# Sheet1.net
KiCad netlist of a schematic drawn in Altium Designer
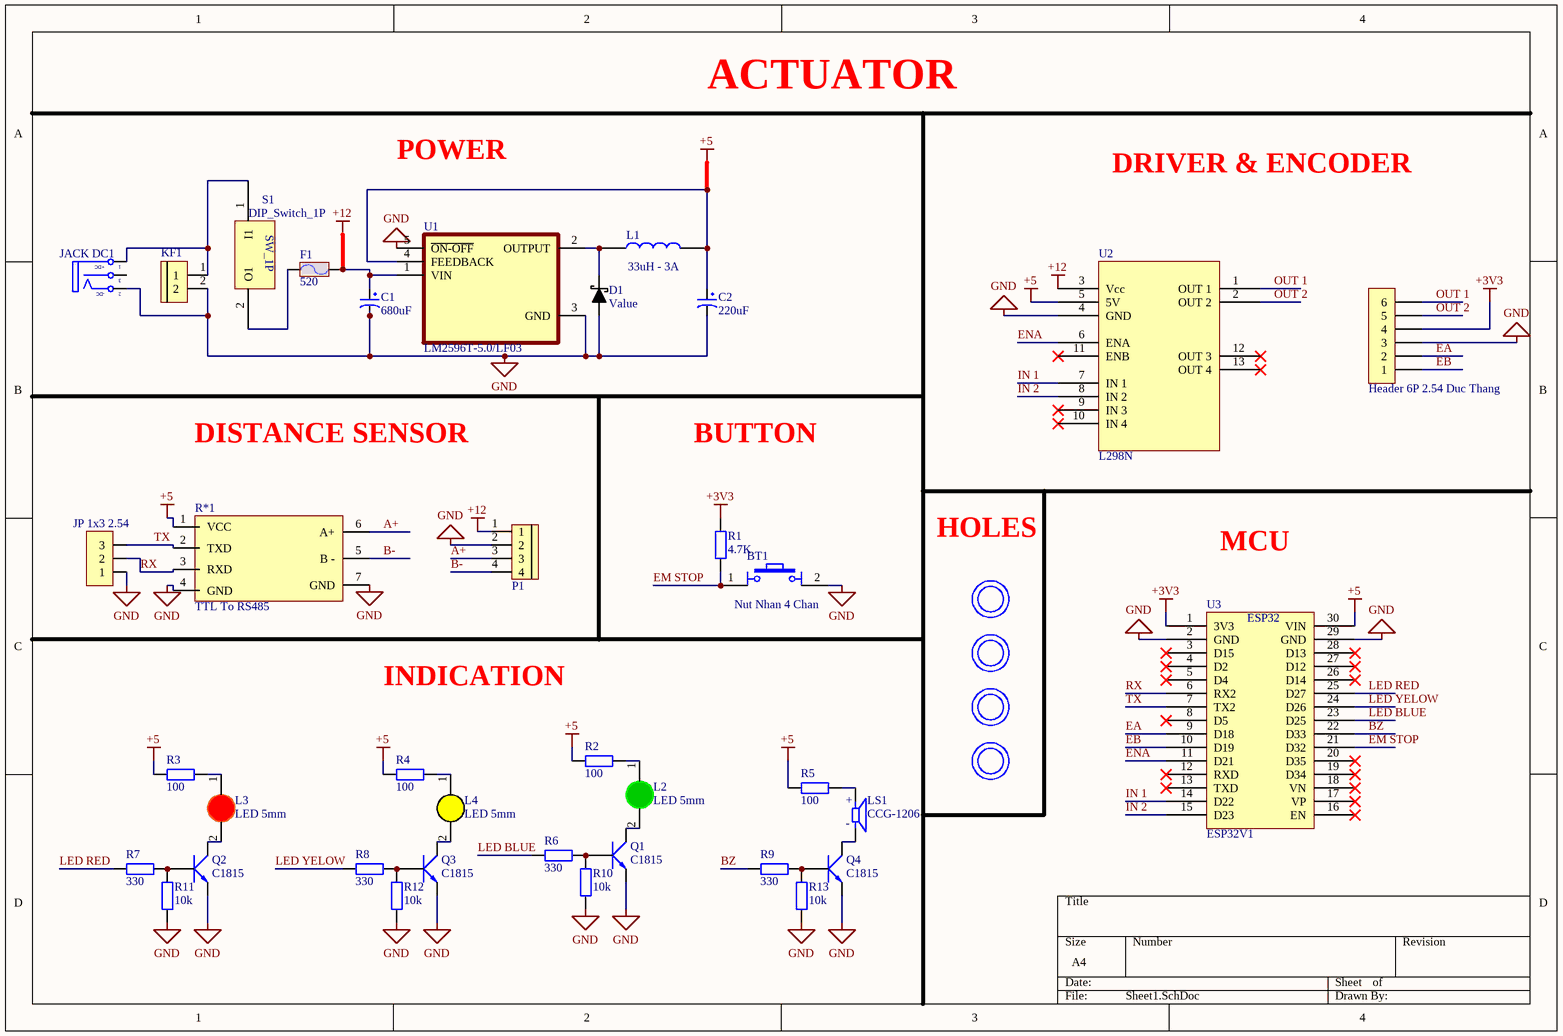
[diagram p0: Sheet1.SchDoc]

(export (version "E")
  (design (tool "Eeschema 10.0.6"))
  (components
    (comp (ref "1")
      (value "Hole")
      (footprint "Hole")
      (description "cắm")
      (libsource (lib "Thinh") (part "Hole"))
    )
    (comp (ref "2")
      (value "Hole")
      (footprint "Hole")
      (description "cắm")
      (libsource (lib "Thinh") (part "Hole"))
    )
    (comp (ref "3")
      (value "Hole")
      (footprint "Hole")
      (description "cắm")
      (libsource (lib "Thinh") (part "Hole"))
    )
    (comp (ref "4")
      (value "Hole")
      (footprint "Hole")
      (description "cắm")
      (libsource (lib "Thinh") (part "Hole"))
    )
    (comp (ref "BT1")
      (value "Nut Nhan 4 Chan")
      (footprint "Nut Nhan 4 Chan Cam 6x6")
      (description "Nut Nhan 4 Chan 6x6mm")
      (libsource (lib "Component") (part "Nut Nhan 4 Chan Cam 6x6"))
    )
    (comp (ref "C1")
      (value "680uF")
      (footprint "tu hoa 13mm")
      (description "Cắm")
      (libsource (lib "Tu dien") (part "Tu Hoa 680uF 25V 13x17"))
    )
    (comp (ref "C2")
      (value "220uF")
      (footprint "tu hoa 6.5mm")
      (description "Cắm")
      (libsource (lib "Tu dien") (part "Tu Hoa 220uF 16V 7x11"))
    )
    (comp (ref "D1")
      (value "Value")
      (footprint "DIODE_SMALL")
      (libsource (lib "Library_Ngocctu") (part "Diode schottky"))
    )
    (comp (ref "F1")
      (value "520")
      (footprint "De Cau Chi 520 630")
      (description "5x20mm")
      (libsource (lib "Component") (part "De Cau Chi 520 630"))
    )
    (comp (ref "H1")
      (value "Header 6P 2.54 Duc Thang")
      (footprint "XH2.54M-6")
      (description "Cắm")
      (libsource (lib "Header") (part "Header 6P 2.54 Duc Thang"))
    )
    (comp (ref "JACK DC1")
      (value "JACK DC 5.5")
      (footprint "JACK DC 5.5")
      (libsource (lib "Component") (part "JACK DC 5.5"))
    )
    (comp (ref "JP1")
      (value "JP 1x3 2.54")
      (footprint "JP 1x3 DT")
      (description "Cắm")
      (libsource (lib "Jump") (part "JP 1x3 2.54 Duc Thang"))
    )
    (comp (ref "KF1")
      (value "CON 2 KF301")
      (footprint "Con 2 KF301 5.08")
      (description "Cắm")
      (libsource (lib "Connector") (part "CON 2 KF301"))
    )
    (comp (ref "L1")
      (value "33uH - 3A")
      (footprint "CUON CAM 100uH3A")
      (description "Cắm")
      (libsource (lib "Cuon Cam") (part "CUON CAM 470uH DIP"))
    )
    (comp (ref "L2")
      (value "LED 5mm")
      (footprint "LED-5MM-Green")
      (description "Cắm")
      (libsource (lib "Led") (part "LED 5mm Xanh La"))
    )
    (comp (ref "L3")
      (value "LED 5mm")
      (footprint "LED-5MM-RED")
      (description "Cắm")
      (libsource (lib "Led") (part "LED 5mm Do"))
    )
    (comp (ref "L4")
      (value "LED 5mm")
      (footprint "LED-5MM-Yellow")
      (description "Cắm")
      (libsource (lib "Led") (part "LED 5mm Vang"))
    )
    (comp (ref "LS1")
      (value "CCG-1206")
      (footprint "CUI_CCG-1206")
      (description "12 mm, 5 V, 85 dB, Through Hole, Sealed, Magnetic Audio Transducer Buzzer")
      (fields (field (name "MF") "Same Sky"))
      (libsource (lib "Thinh") (part "CCG-1206"))
    )
    (comp (ref "P1")
      (value "CON 4 EDG5.08")
      (footprint "CON 4 4EDG5.08 - THANG")
      (description "Cắm")
      (libsource (lib "Connector") (part "CON 4 EDG5.08"))
    )
    (comp (ref "Q1")
      (value "C1815")
      (footprint "TO92")
      (description "NPN transistor")
      (libsource (lib "TranFet") (part "C1815"))
    )
    (comp (ref "Q2")
      (value "C1815")
      (footprint "TO92")
      (description "NPN transistor")
      (libsource (lib "TranFet") (part "C1815"))
    )
    (comp (ref "Q3")
      (value "C1815")
      (footprint "TO92")
      (description "NPN transistor")
      (libsource (lib "TranFet") (part "C1815"))
    )
    (comp (ref "Q4")
      (value "C1815")
      (footprint "TO92")
      (description "NPN transistor")
      (libsource (lib "TranFet") (part "C1815"))
    )
    (comp (ref "R*1")
      (value "TTL To RS485")
      (footprint "TTL TO RS485_Module")
      (libsource (lib "NGUYENDAINGHIA") (part "TTL To RS485"))
    )
    (comp (ref "R1")
      (value "4.7K")
      (footprint "tro vach 1/4w")
      (description "Cắm")
      (libsource (lib "Dien Tro") (part "Tro Vach 1/4W 5% 100R"))
    )
    (comp (ref "R2")
      (value "100")
      (footprint "tro vach 1/4w")
      (description "Cắm")
      (libsource (lib "Dien Tro") (part "Tro Vach 1/4W 5% 100R"))
    )
    (comp (ref "R3")
      (value "100")
      (footprint "tro vach 1/4w")
      (description "Cắm")
      (libsource (lib "Dien Tro") (part "Tro Vach 1/4W 5% 100R"))
    )
    (comp (ref "R4")
      (value "100")
      (footprint "tro vach 1/4w")
      (description "Cắm")
      (libsource (lib "Dien Tro") (part "Tro Vach 1/4W 5% 100R"))
    )
    (comp (ref "R5")
      (value "100")
      (footprint "tro vach 1/4w")
      (description "Cắm")
      (libsource (lib "Dien Tro") (part "Tro Vach 1/4W 5% 100R"))
    )
    (comp (ref "R6")
      (value "330")
      (footprint "tro vach 1/4w")
      (description "Cắm")
      (libsource (lib "Dien Tro") (part "Tro Vach 1/4W 5% 100R"))
    )
    (comp (ref "R7")
      (value "330")
      (footprint "tro vach 1/4w")
      (description "Cắm")
      (libsource (lib "Dien Tro") (part "Tro Vach 1/4W 5% 100R"))
    )
    (comp (ref "R8")
      (value "330")
      (footprint "tro vach 1/4w")
      (description "Cắm")
      (libsource (lib "Dien Tro") (part "Tro Vach 1/4W 5% 100R"))
    )
    (comp (ref "R9")
      (value "330")
      (footprint "tro vach 1/4w")
      (description "Cắm")
      (libsource (lib "Dien Tro") (part "Tro Vach 1/4W 5% 100R"))
    )
    (comp (ref "R10")
      (value "10k")
      (footprint "tro vach 1/4w")
      (description "Cắm")
      (libsource (lib "Dien Tro") (part "Tro Vach 1/4W 5% 100R"))
    )
    (comp (ref "R11")
      (value "10k")
      (footprint "tro vach 1/4w")
      (description "Cắm")
      (libsource (lib "Dien Tro") (part "Tro Vach 1/4W 5% 100R"))
    )
    (comp (ref "R12")
      (value "10k")
      (footprint "tro vach 1/4w")
      (description "Cắm")
      (libsource (lib "Dien Tro") (part "Tro Vach 1/4W 5% 100R"))
    )
    (comp (ref "R13")
      (value "10k")
      (footprint "tro vach 1/4w")
      (description "Cắm")
      (libsource (lib "Dien Tro") (part "Tro Vach 1/4W 5% 100R"))
    )
    (comp (ref "S1")
      (value "DIP_Switch_1P")
      (footprint "DIP_Switch_1P")
      (description "cắm")
      (libsource (lib "Thinh") (part "DIP_Switch_1P"))
    )
    (comp (ref "U1")
      (value "LM2596T-5.0/LF03")
      (footprint "TO170P1016X470X2092-5")
      (description "SIMPLE SWITCHERÂ® 4.5V to 40V, 3A Low Component Count Step-Down Regulator")
      (fields (field (name "MF") "Texas Instruments"))
      (libsource (lib "Thinh") (part "LM2596T-5.0/LF03"))
    )
    (comp (ref "U2")
      (value "L298N")
      (footprint "L298N")
      (description "Cắm")
      (libsource (lib "Thinh") (part "L298N"))
    )
    (comp (ref "U3")
      (value "ESP32V1")
      (footprint "ESP32V1")
      (description "cắm")
      (libsource (lib "Thinh") (part "ESP32V1"))
    )
  )
  (nets
    (net (code "1") (name "+3V3") (class "Default")
      (node (ref "H1") (pin "4") (pinfunction "4_4") (pintype "passive"))
      (node (ref "R1") (pin "1") (pinfunction "1_1") (pintype "passive"))
      (node (ref "U3") (pin "1") (pinfunction "3V3_1") (pintype "passive"))
    )
    (net (code "2") (name "+5") (class "Default")
      (node (ref "C2") (pin "1") (pinfunction "1_1") (pintype "passive"))
      (node (ref "L1") (pin "2") (pinfunction "2_2") (pintype "passive"))
      (node (ref "R*1") (pin "1") (pinfunction "VCC_1") (pintype "passive"))
      (node (ref "R2") (pin "2") (pinfunction "2_2") (pintype "passive"))
      (node (ref "R3") (pin "2") (pinfunction "2_2") (pintype "passive"))
      (node (ref "R4") (pin "2") (pinfunction "2_2") (pintype "passive"))
      (node (ref "R5") (pin "2") (pinfunction "2_2") (pintype "passive"))
      (node (ref "U1") (pin "4") (pinfunction "FEEDBACK_4") (pintype "passive"))
      (node (ref "U2") (pin "5") (pinfunction "5V_5") (pintype "passive"))
      (node (ref "U3") (pin "30") (pinfunction "VIN_30") (pintype "passive"))
    )
    (net (code "3") (name "+12") (class "Default")
      (node (ref "C1") (pin "1") (pinfunction "1_1") (pintype "passive"))
      (node (ref "F1") (pin "2") (pinfunction "2_2") (pintype "passive"))
      (node (ref "P1") (pin "1") (pinfunction "1_1") (pintype "passive"))
      (node (ref "U1") (pin "1") (pinfunction "VIN_1") (pintype "passive"))
      (node (ref "U2") (pin "3") (pinfunction "Vcc_3") (pintype "passive"))
    )
    (net (code "4") (name "/A+") (class "Default")
      (node (ref "P1") (pin "3") (pinfunction "3_3") (pintype "passive"))
      (node (ref "R*1") (pin "6") (pinfunction "A+_6") (pintype "passive"))
    )
    (net (code "6") (name "/B-") (class "Default")
      (node (ref "P1") (pin "4") (pinfunction "4_4") (pintype "passive"))
      (node (ref "R*1") (pin "5") (pinfunction "B_-_5") (pintype "passive"))
    )
    (net (code "7") (name "/BZ") (class "Default")
      (node (ref "R9") (pin "2") (pinfunction "2_2") (pintype "passive"))
      (node (ref "U3") (pin "22") (pinfunction "D33_22") (pintype "passive"))
    )
    (net (code "8") (name "/EA") (class "Default")
      (node (ref "H1") (pin "2") (pinfunction "2_2") (pintype "passive"))
      (node (ref "U3") (pin "9") (pinfunction "D18_9") (pintype "passive"))
    )
    (net (code "9") (name "/EB") (class "Default")
      (node (ref "H1") (pin "1") (pinfunction "1_1") (pintype "passive"))
      (node (ref "U3") (pin "10") (pinfunction "D19_10") (pintype "passive"))
    )
    (net (code "10") (name "/EM STOP") (class "Default")
      (node (ref "BT1") (pin "1") (pintype "passive"))
      (node (ref "R1") (pin "2") (pinfunction "2_2") (pintype "passive"))
      (node (ref "U3") (pin "21") (pinfunction "D32_21") (pintype "passive"))
    )
    (net (code "11") (name "/ENA") (class "Default")
      (node (ref "U2") (pin "6") (pinfunction "ENA_6") (pintype "passive"))
      (node (ref "U3") (pin "11") (pinfunction "D21_11") (pintype "passive"))
    )
    (net (code "12") (name "/IN 1") (class "Default")
      (node (ref "U2") (pin "7") (pinfunction "IN_1_7") (pintype "passive"))
      (node (ref "U3") (pin "14") (pinfunction "D22_14") (pintype "passive"))
    )
    (net (code "13") (name "/IN 2") (class "Default")
      (node (ref "U2") (pin "8") (pinfunction "IN_2_8") (pintype "passive"))
      (node (ref "U3") (pin "15") (pinfunction "D23_15") (pintype "passive"))
    )
    (net (code "14") (name "/LED BLUE") (class "Default")
      (node (ref "R6") (pin "2") (pinfunction "2_2") (pintype "passive"))
      (node (ref "U3") (pin "23") (pinfunction "D25_23") (pintype "passive"))
    )
    (net (code "15") (name "/LED RED") (class "Default")
      (node (ref "R7") (pin "2") (pinfunction "2_2") (pintype "passive"))
      (node (ref "U3") (pin "25") (pinfunction "D27_25") (pintype "passive"))
    )
    (net (code "16") (name "/LED YELOW") (class "Default")
      (node (ref "R8") (pin "2") (pinfunction "2_2") (pintype "passive"))
      (node (ref "U3") (pin "24") (pinfunction "D26_24") (pintype "passive"))
    )
    (net (code "17") (name "/OUT 1") (class "Default")
      (node (ref "H1") (pin "6") (pinfunction "6_6") (pintype "passive"))
      (node (ref "U2") (pin "1") (pinfunction "OUT_1_1") (pintype "passive"))
    )
    (net (code "18") (name "/OUT 2") (class "Default")
      (node (ref "H1") (pin "5") (pinfunction "5_5") (pintype "passive"))
      (node (ref "U2") (pin "2") (pinfunction "OUT_2_2") (pintype "passive"))
    )
    (net (code "19") (name "/RX") (class "Default")
      (node (ref "JP1") (pin "2") (pinfunction "2_2") (pintype "passive"))
      (node (ref "R*1") (pin "3") (pinfunction "RXD_3") (pintype "passive"))
      (node (ref "U3") (pin "6") (pinfunction "RX2_6") (pintype "passive"))
    )
    (net (code "20") (name "/TX") (class "Default")
      (node (ref "JP1") (pin "3") (pinfunction "3_3") (pintype "passive"))
      (node (ref "R*1") (pin "2") (pinfunction "TXD_2") (pintype "passive"))
      (node (ref "U3") (pin "7") (pinfunction "TX2_7") (pintype "passive"))
    )
    (net (code "21") (name "GND") (class "Default")
      (node (ref "BT1") (pin "2") (pintype "passive"))
      (node (ref "C1") (pin "2") (pinfunction "2_2") (pintype "passive"))
      (node (ref "C2") (pin "2") (pinfunction "2_2") (pintype "passive"))
      (node (ref "D1") (pin "1") (pinfunction "A_1") (pintype "passive"))
      (node (ref "H1") (pin "3") (pinfunction "3_3") (pintype "passive"))
      (node (ref "JACK DC1") (pin "2") (pinfunction "TN_2") (pintype "passive"))
      (node (ref "JP1") (pin "1") (pinfunction "1_1") (pintype "passive"))
      (node (ref "KF1") (pin "2") (pinfunction "2_2") (pintype "passive"))
      (node (ref "P1") (pin "2") (pinfunction "2_2") (pintype "passive"))
      (node (ref "Q1") (pin "1") (pinfunction "E_1") (pintype "passive"))
      (node (ref "Q2") (pin "1") (pinfunction "E_1") (pintype "passive"))
      (node (ref "Q3") (pin "1") (pinfunction "E_1") (pintype "passive"))
      (node (ref "Q4") (pin "1") (pinfunction "E_1") (pintype "passive"))
      (node (ref "R*1") (pin "4") (pinfunction "GND_4") (pintype "passive"))
      (node (ref "R*1") (pin "7") (pinfunction "GND_7") (pintype "passive"))
      (node (ref "R10") (pin "1") (pinfunction "1_1") (pintype "passive"))
      (node (ref "R11") (pin "1") (pinfunction "1_1") (pintype "passive"))
      (node (ref "R12") (pin "1") (pinfunction "1_1") (pintype "passive"))
      (node (ref "R13") (pin "1") (pinfunction "1_1") (pintype "passive"))
      (node (ref "U1") (pin "3") (pinfunction "GND_3") (pintype "passive"))
      (node (ref "U1") (pin "5") (pinfunction "~{ON-OFF}_5") (pintype "passive"))
      (node (ref "U2") (pin "4") (pinfunction "GND_4") (pintype "passive"))
      (node (ref "U3") (pin "2") (pinfunction "GND_2") (pintype "passive"))
      (node (ref "U3") (pin "29") (pinfunction "GND_29") (pintype "passive"))
    )
    (net (code "22") (name "Net-(D1-K)") (class "Default")
      (node (ref "D1") (pin "2") (pinfunction "K_2") (pintype "passive"))
      (node (ref "L1") (pin "1") (pinfunction "1_1") (pintype "passive"))
      (node (ref "U1") (pin "2") (pinfunction "OUTPUT_2") (pintype "passive"))
    )
    (net (code "23") (name "Net-(JACK DC1-T)") (class "Default")
      (node (ref "JACK DC1") (pin "1") (pinfunction "T_1") (pintype "passive"))
      (node (ref "KF1") (pin "1") (pinfunction "1_1") (pintype "passive"))
      (node (ref "S1") (pin "1") (pinfunction "I1_1") (pintype "passive"))
    )
    (net (code "24") (name "Net-(L2-A)") (class "Default")
      (node (ref "L2") (pin "1") (pinfunction "A_1") (pintype "passive"))
      (node (ref "R2") (pin "1") (pinfunction "1_1") (pintype "passive"))
    )
    (net (code "25") (name "Net-(L2-K)") (class "Default")
      (node (ref "L2") (pin "2") (pinfunction "K_2") (pintype "passive"))
      (node (ref "Q1") (pin "2") (pinfunction "C_2") (pintype "passive"))
    )
    (net (code "26") (name "Net-(L3-A)") (class "Default")
      (node (ref "L3") (pin "1") (pinfunction "A_1") (pintype "passive"))
      (node (ref "R3") (pin "1") (pinfunction "1_1") (pintype "passive"))
    )
    (net (code "27") (name "Net-(L3-K)") (class "Default")
      (node (ref "L3") (pin "2") (pinfunction "K_2") (pintype "passive"))
      (node (ref "Q2") (pin "2") (pinfunction "C_2") (pintype "passive"))
    )
    (net (code "28") (name "Net-(L4-A)") (class "Default")
      (node (ref "L4") (pin "1") (pinfunction "A_1") (pintype "passive"))
      (node (ref "R4") (pin "1") (pinfunction "1_1") (pintype "passive"))
    )
    (net (code "29") (name "Net-(L4-K)") (class "Default")
      (node (ref "L4") (pin "2") (pinfunction "K_2") (pintype "passive"))
      (node (ref "Q3") (pin "2") (pinfunction "C_2") (pintype "passive"))
    )
    (net (code "30") (name "Net-(LS1-PadP)") (class "Default")
      (node (ref "LS1") (pin "P") (pinfunction "P_P") (pintype "passive"))
      (node (ref "R5") (pin "1") (pinfunction "1_1") (pintype "passive"))
    )
    (net (code "31") (name "Net-(Q1-B)") (class "Default")
      (node (ref "Q1") (pin "3") (pinfunction "B_3") (pintype "passive"))
      (node (ref "R10") (pin "2") (pinfunction "2_2") (pintype "passive"))
      (node (ref "R6") (pin "1") (pinfunction "1_1") (pintype "passive"))
    )
    (net (code "32") (name "Net-(Q2-B)") (class "Default")
      (node (ref "Q2") (pin "3") (pinfunction "B_3") (pintype "passive"))
      (node (ref "R11") (pin "2") (pinfunction "2_2") (pintype "passive"))
      (node (ref "R7") (pin "1") (pinfunction "1_1") (pintype "passive"))
    )
    (net (code "33") (name "Net-(Q3-B)") (class "Default")
      (node (ref "Q3") (pin "3") (pinfunction "B_3") (pintype "passive"))
      (node (ref "R12") (pin "2") (pinfunction "2_2") (pintype "passive"))
      (node (ref "R8") (pin "1") (pinfunction "1_1") (pintype "passive"))
    )
    (net (code "34") (name "Net-(Q4-B)") (class "Default")
      (node (ref "Q4") (pin "3") (pinfunction "B_3") (pintype "passive"))
      (node (ref "R13") (pin "2") (pinfunction "2_2") (pintype "passive"))
      (node (ref "R9") (pin "1") (pinfunction "1_1") (pintype "passive"))
    )
    (net (code "35") (name "Net-(Q4-C)") (class "Default")
      (node (ref "LS1") (pin "M") (pinfunction "M_M") (pintype "passive"))
      (node (ref "Q4") (pin "2") (pinfunction "C_2") (pintype "passive"))
    )
    (net (code "36") (name "Net-(S1-O1)") (class "Default")
      (node (ref "F1") (pin "1") (pinfunction "1_1") (pintype "passive"))
      (node (ref "S1") (pin "2") (pinfunction "O1_2") (pintype "passive"))
    )
    (net (code "37") (name "unconnected-(JACK DC1-S-Pad3)") (class "Default")
      (node (ref "JACK DC1") (pin "3") (pinfunction "S_3") (pintype "power_in"))
    )
    (net (code "38") (name "unconnected-(U2-ENB-Pad11)") (class "Default")
      (node (ref "U2") (pin "11") (pinfunction "ENB_11") (pintype "passive+no_connect"))
    )
    (net (code "39") (name "unconnected-(U2-IN_3-Pad9)") (class "Default")
      (node (ref "U2") (pin "9") (pinfunction "IN_3_9") (pintype "passive+no_connect"))
    )
    (net (code "40") (name "unconnected-(U2-IN_4-Pad10)") (class "Default")
      (node (ref "U2") (pin "10") (pinfunction "IN_4_10") (pintype "passive+no_connect"))
    )
    (net (code "41") (name "unconnected-(U2-OUT_3-Pad12)") (class "Default")
      (node (ref "U2") (pin "12") (pinfunction "OUT_3_12") (pintype "passive+no_connect"))
    )
    (net (code "42") (name "unconnected-(U2-OUT_4-Pad13)") (class "Default")
      (node (ref "U2") (pin "13") (pinfunction "OUT_4_13") (pintype "passive+no_connect"))
    )
    (net (code "43") (name "unconnected-(U3-D2-Pad4)") (class "Default")
      (node (ref "U3") (pin "4") (pinfunction "D2_4") (pintype "passive+no_connect"))
    )
    (net (code "44") (name "unconnected-(U3-D4-Pad5)") (class "Default")
      (node (ref "U3") (pin "5") (pinfunction "D4_5") (pintype "passive+no_connect"))
    )
    (net (code "45") (name "unconnected-(U3-D5-Pad8)") (class "Default")
      (node (ref "U3") (pin "8") (pinfunction "D5_8") (pintype "passive+no_connect"))
    )
    (net (code "46") (name "unconnected-(U3-D12-Pad27)") (class "Default")
      (node (ref "U3") (pin "27") (pinfunction "D12_27") (pintype "passive+no_connect"))
    )
    (net (code "47") (name "unconnected-(U3-D13-Pad28)") (class "Default")
      (node (ref "U3") (pin "28") (pinfunction "D13_28") (pintype "passive+no_connect"))
    )
    (net (code "48") (name "unconnected-(U3-D14-Pad26)") (class "Default")
      (node (ref "U3") (pin "26") (pinfunction "D14_26") (pintype "passive+no_connect"))
    )
    (net (code "49") (name "unconnected-(U3-D15-Pad3)") (class "Default")
      (node (ref "U3") (pin "3") (pinfunction "D15_3") (pintype "passive+no_connect"))
    )
    (net (code "50") (name "unconnected-(U3-D34-Pad19)") (class "Default")
      (node (ref "U3") (pin "19") (pinfunction "D34_19") (pintype "passive+no_connect"))
    )
    (net (code "51") (name "unconnected-(U3-D35-Pad20)") (class "Default")
      (node (ref "U3") (pin "20") (pinfunction "D35_20") (pintype "passive+no_connect"))
    )
    (net (code "52") (name "unconnected-(U3-EN-Pad16)") (class "Default")
      (node (ref "U3") (pin "16") (pinfunction "EN_16") (pintype "passive+no_connect"))
    )
    (net (code "53") (name "unconnected-(U3-RXD-Pad12)") (class "Default")
      (node (ref "U3") (pin "12") (pinfunction "RXD_12") (pintype "passive+no_connect"))
    )
    (net (code "54") (name "unconnected-(U3-TXD-Pad13)") (class "Default")
      (node (ref "U3") (pin "13") (pinfunction "TXD_13") (pintype "passive+no_connect"))
    )
    (net (code "55") (name "unconnected-(U3-VN-Pad18)") (class "Default")
      (node (ref "U3") (pin "18") (pinfunction "VN_18") (pintype "passive+no_connect"))
    )
    (net (code "56") (name "unconnected-(U3-VP-Pad17)") (class "Default")
      (node (ref "U3") (pin "17") (pinfunction "VP_17") (pintype "passive+no_connect"))
    )
  )
)
